# RCJS_ComMod_Helios_250821A.net
KiCad netlist of a schematic drawn in EasyEDA Pro
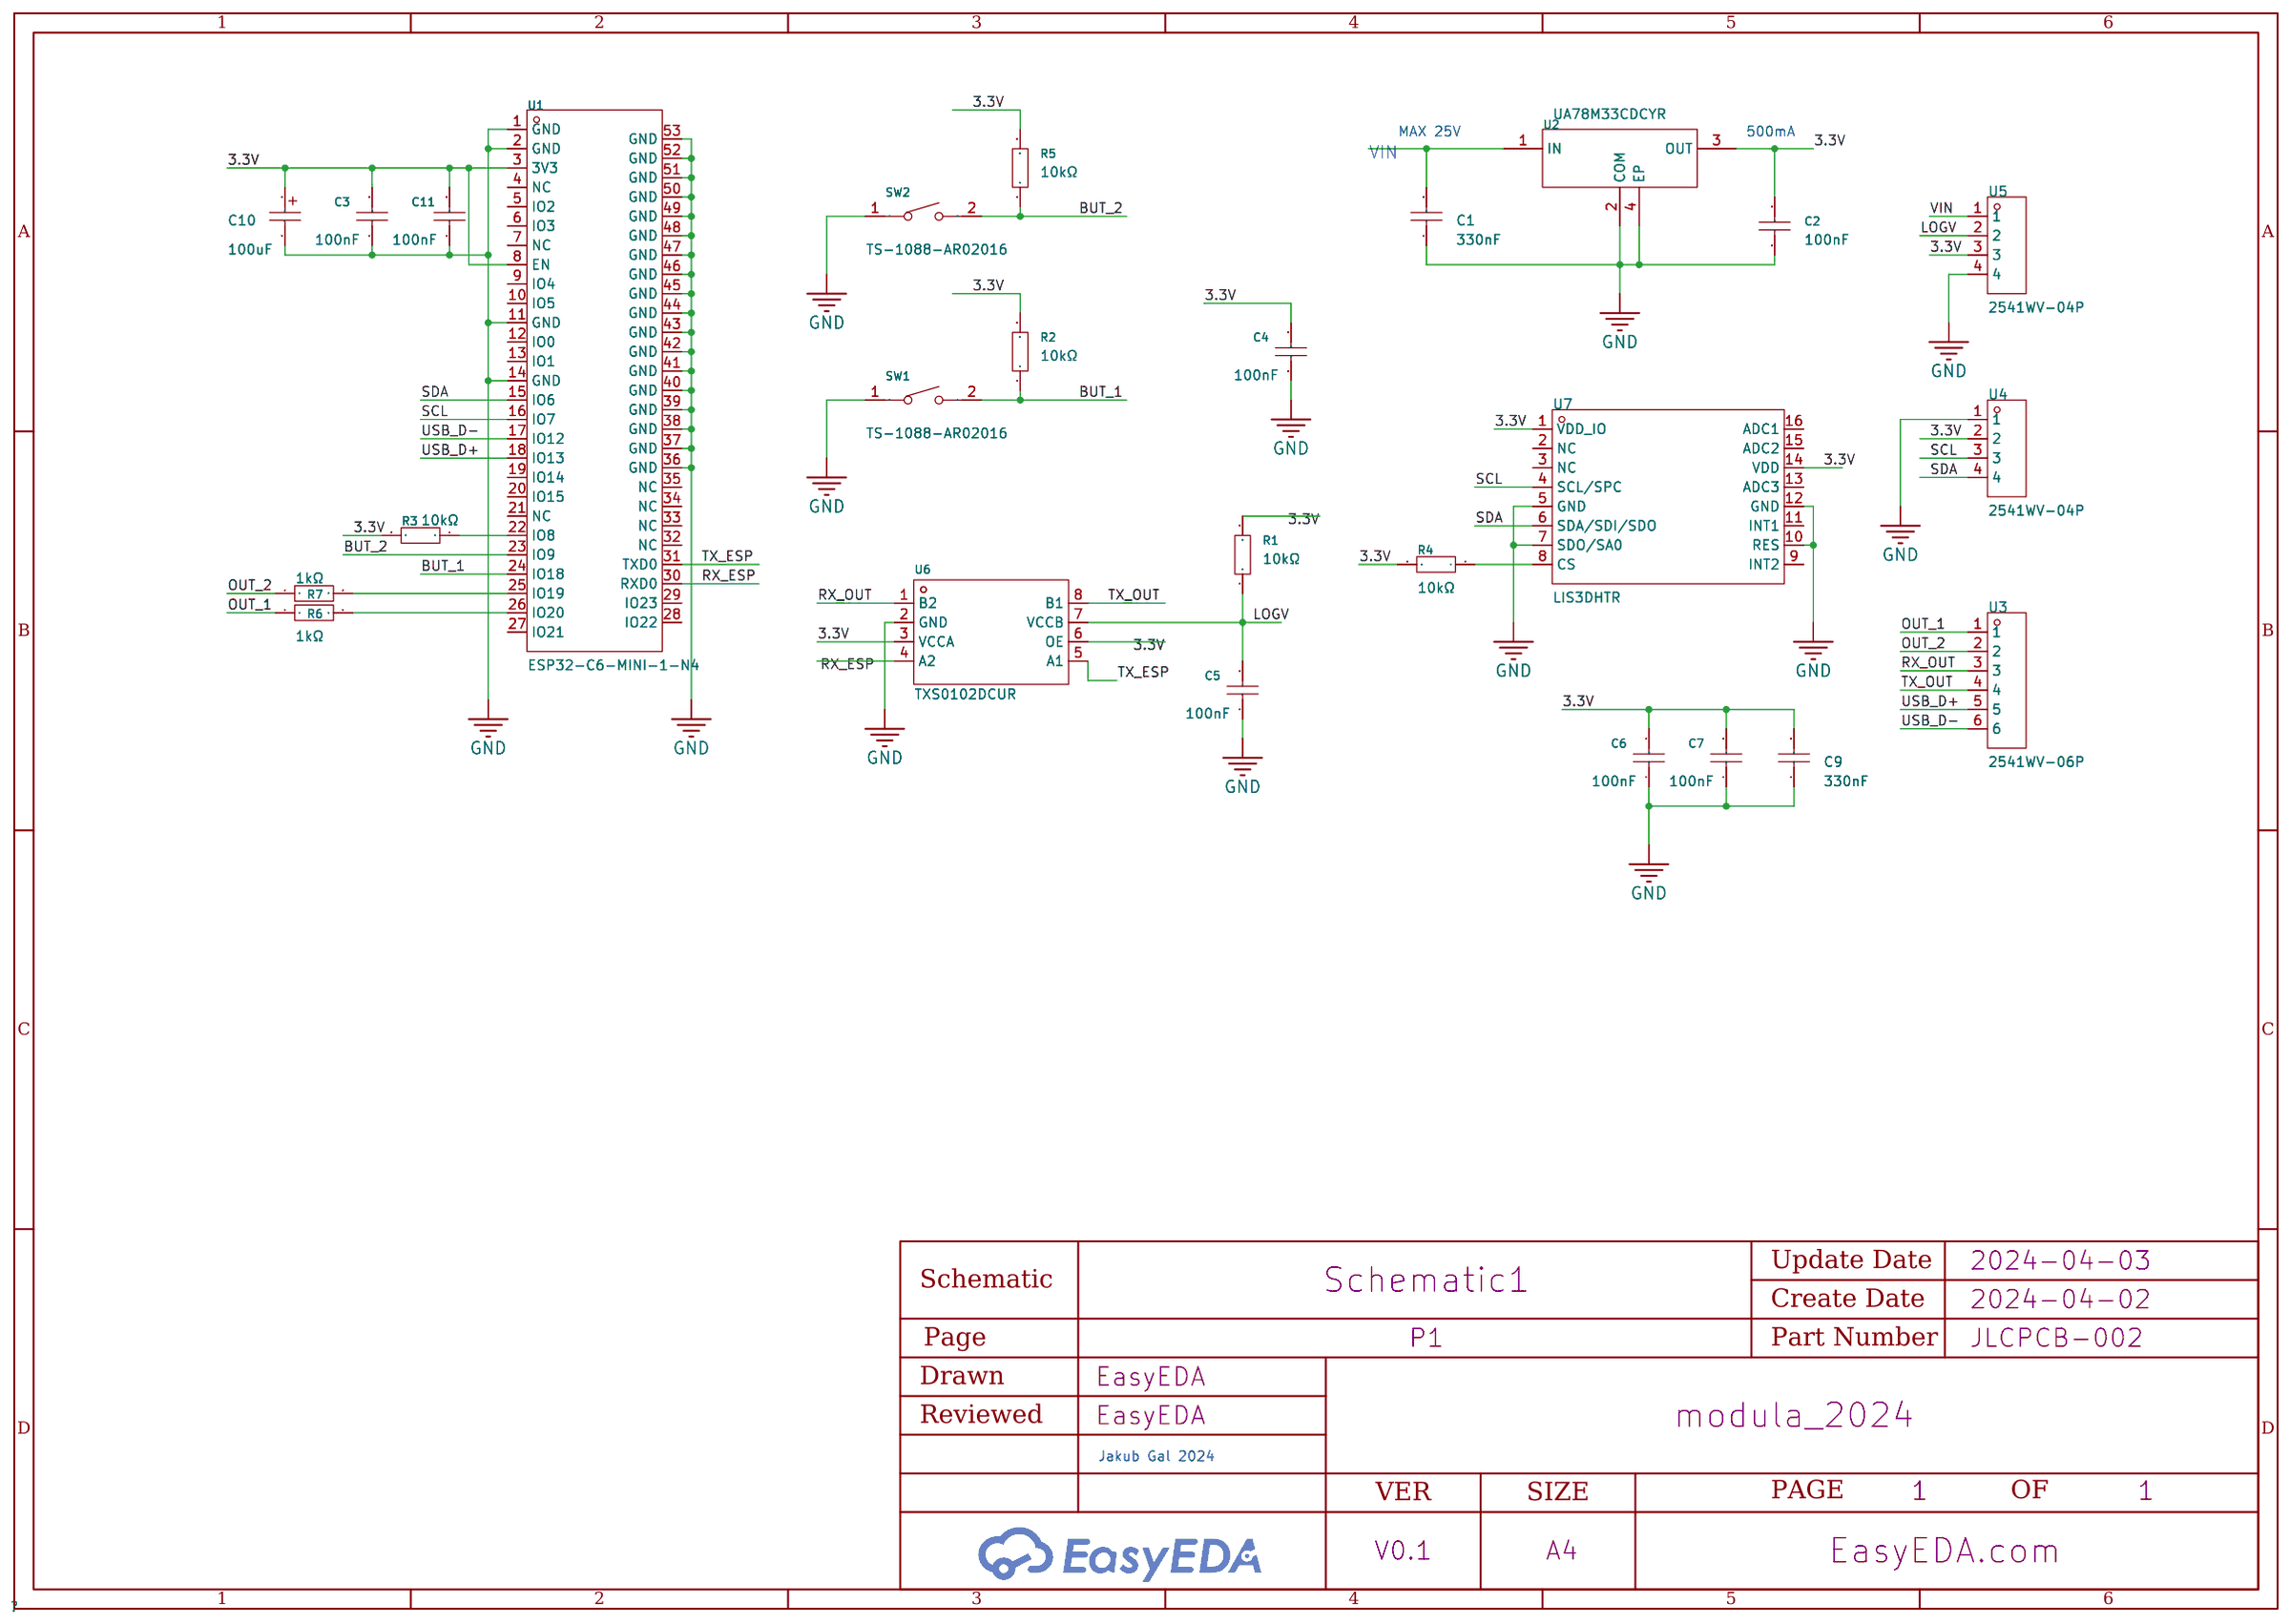
[diagram p0: schematic sheet]

(export (version "E")
  (design (tool "Eeschema 10.0.6"))
  (components
    (comp (ref "C1")
      (value "330nF")
      (footprint "easyedapro:C0805")
      (fields (field (name "Manufacturer Part") "0805B334K500NT") (field (name "Manufacturer") "FH(风华)"))
      (libsource (lib "easyedapro") (part "0805B334K500NT"))
    )
    (comp (ref "C2")
      (value "100nF")
      (footprint "easyedapro:C0603")
      (fields (field (name "Manufacturer Part") "0603B104K500NT") (field (name "Manufacturer") "FH(风华)"))
      (libsource (lib "easyedapro") (part "0603B104K500NT"))
    )
    (comp (ref "C3")
      (value "100nF")
      (footprint "easyedapro:C0603")
      (fields (field (name "Manufacturer Part") "0603B104K500NT") (field (name "Manufacturer") "FH(风华)"))
      (libsource (lib "easyedapro") (part "0603B104K500NT"))
    )
    (comp (ref "C4")
      (value "100nF")
      (footprint "easyedapro:C0603")
      (fields (field (name "Manufacturer Part") "0603B104K500NT") (field (name "Manufacturer") "FH(风华)"))
      (libsource (lib "easyedapro") (part "0603B104K500NT"))
    )
    (comp (ref "C5")
      (value "100nF")
      (footprint "easyedapro:C0603")
      (fields (field (name "Manufacturer Part") "0603B104K500NT") (field (name "Manufacturer") "FH(风华)"))
      (libsource (lib "easyedapro") (part "0603B104K500NT"))
    )
    (comp (ref "C6")
      (value "100nF")
      (footprint "easyedapro:C0603")
      (fields (field (name "Manufacturer Part") "0603B104K500NT") (field (name "Manufacturer") "FH(风华)"))
      (libsource (lib "easyedapro") (part "0603B104K500NT"))
    )
    (comp (ref "C7")
      (value "100nF")
      (footprint "easyedapro:C0603")
      (fields (field (name "Manufacturer Part") "0603B104K500NT") (field (name "Manufacturer") "FH(风华)"))
      (libsource (lib "easyedapro") (part "0603B104K500NT"))
    )
    (comp (ref "C9")
      (value "330nF")
      (footprint "easyedapro:C0805")
      (fields (field (name "Manufacturer Part") "0805B334K500NT") (field (name "Manufacturer") "FH(风华)"))
      (libsource (lib "easyedapro") (part "0805B334K500NT"))
    )
    (comp (ref "C10")
      (value "100uF")
      (footprint "easyedapro:CAP-SMD_L3.5-W2.8-R-RD")
      (fields
        (field (name "Manufacturer Part") "CA45-B-6.3V-100uF-K")
        (field (name "Manufacturer") "CEC(振华新云)")
      )
      (libsource (lib "easyedapro") (part "CA45-B-6.3V-100UF-K"))
    )
    (comp (ref "C11")
      (value "100nF")
      (footprint "easyedapro:C0603")
      (fields (field (name "Manufacturer Part") "0603B104K500NT") (field (name "Manufacturer") "FH(风华)"))
      (libsource (lib "easyedapro") (part "0603B104K500NT"))
    )
    (comp (ref "R1")
      (value "10kΩ")
      (footprint "easyedapro:R0603")
      (fields
        (field (name "Manufacturer Part") "0603WAF1002T5E")
        (field (name "Manufacturer") "UNI-ROYAL(厚声)")
      )
      (libsource (lib "easyedapro") (part "0603WAF1002T5E"))
    )
    (comp (ref "R2")
      (value "10kΩ")
      (footprint "easyedapro:R0603")
      (fields
        (field (name "Manufacturer Part") "0603WAF1002T5E")
        (field (name "Manufacturer") "UNI-ROYAL(厚声)")
      )
      (libsource (lib "easyedapro") (part "0603WAF1002T5E"))
    )
    (comp (ref "R3")
      (value "10kΩ")
      (footprint "easyedapro:R0603")
      (fields
        (field (name "Manufacturer Part") "0603WAF1002T5E")
        (field (name "Manufacturer") "UNI-ROYAL(厚声)")
      )
      (libsource (lib "easyedapro") (part "0603WAF1002T5E"))
    )
    (comp (ref "R4")
      (value "10kΩ")
      (footprint "easyedapro:R0603")
      (fields
        (field (name "Manufacturer Part") "0603WAF1002T5E")
        (field (name "Manufacturer") "UNI-ROYAL(厚声)")
      )
      (libsource (lib "easyedapro") (part "0603WAF1002T5E"))
    )
    (comp (ref "R5")
      (value "10kΩ")
      (footprint "easyedapro:R0603")
      (fields
        (field (name "Manufacturer Part") "0603WAF1002T5E")
        (field (name "Manufacturer") "UNI-ROYAL(厚声)")
      )
      (libsource (lib "easyedapro") (part "0603WAF1002T5E"))
    )
    (comp (ref "R6")
      (value "1kΩ")
      (footprint "easyedapro:R0603")
      (fields
        (field (name "Manufacturer Part") "0603WAJ0102T5E")
        (field (name "Manufacturer") "UNI-ROYAL(厚声)")
      )
      (libsource (lib "easyedapro") (part "0603WAJ0102T5E"))
    )
    (comp (ref "R7")
      (value "1kΩ")
      (footprint "easyedapro:R0603")
      (fields
        (field (name "Manufacturer Part") "0603WAJ0102T5E")
        (field (name "Manufacturer") "UNI-ROYAL(厚声)")
      )
      (libsource (lib "easyedapro") (part "0603WAJ0102T5E"))
    )
    (comp (ref "SW1")
      (value "TS-1088-AR02016")
      (footprint "easyedapro:SW-SMD_L3.9-W3.0-P4.45")
      (fields (field (name "Manufacturer") "XUNPU(讯普)"))
      (libsource (lib "easyedapro") (part "TS-1088-AR02016"))
    )
    (comp (ref "SW2")
      (value "TS-1088-AR02016")
      (footprint "easyedapro:SW-SMD_L3.9-W3.0-P4.45")
      (fields (field (name "Manufacturer") "XUNPU(讯普)"))
      (libsource (lib "easyedapro") (part "TS-1088-AR02016"))
    )
    (comp (ref "U1")
      (value "ESP32-C6-MINI-1-N4")
      (footprint "easyedapro:WIFIM-SMD_61P-L16.6-W13.2-P0.80-ESP32-C6-MINI-1-N4")
      (fields (field (name "Manufacturer") "ESPRESSIF(乐鑫)"))
      (libsource (lib "easyedapro") (part "ESP32-C6-MINI-1-N4"))
    )
    (comp (ref "U2")
      (value "UA78M33CDCYR")
      (footprint "easyedapro:SOT-223_L6.5-W3.5-P2.30-LS7.0-BR")
      (fields (field (name "Manufacturer") "TI(德州仪器)"))
      (libsource (lib "easyedapro") (part "UA78M33CDCYR"))
    )
    (comp (ref "U3")
      (value "2541WV-06P")
      (footprint "easyedapro:HDR-TH_6P-P2.54-V-M")
      (fields (field (name "Manufacturer") "HanElectricity(瀚源)"))
      (libsource (lib "easyedapro") (part "2541WV-06P"))
    )
    (comp (ref "U4")
      (value "2541WV-04P")
      (footprint "easyedapro:HDR-TH_4P-P2.54-V-M-1")
      (fields (field (name "Manufacturer") "HanElectricity(瀚源)"))
      (libsource (lib "easyedapro") (part "2541WV-04P"))
    )
    (comp (ref "U5")
      (value "2541WV-04P")
      (footprint "easyedapro:HDR-TH_4P-P2.54-V-M-1")
      (fields (field (name "Manufacturer") "HanElectricity(瀚源)"))
      (libsource (lib "easyedapro") (part "2541WV-04P"))
    )
    (comp (ref "U6")
      (value "TXS0102DCUR")
      (footprint "easyedapro:VSON8_L2.0-W2.3-P0.50-LS3.1-BL")
      (fields (field (name "Manufacturer") "TI(德州仪器)"))
      (libsource (lib "easyedapro") (part "TXS0102DCUR"))
    )
    (comp (ref "U7")
      (value "LIS3DHTR")
      (footprint "easyedapro:LGA-16_L3.0-W3.0-P0.50-TL")
      (fields (field (name "Manufacturer") "ST(意法半导体)"))
      (libsource (lib "easyedapro") (part "LIS3DHTR_C15134"))
    )
  )
  (nets
    (net (code "1") (name "/3.3V") (class "Default")
      (node (ref "C10") (pin "1") (pinfunction "1_1") (pintype "input"))
      (node (ref "C11") (pin "2") (pinfunction "2_2") (pintype "input"))
      (node (ref "C2") (pin "2") (pinfunction "2_2") (pintype "input"))
      (node (ref "C3") (pin "2") (pinfunction "2_2") (pintype "input"))
      (node (ref "C4") (pin "2") (pinfunction "2_2") (pintype "input"))
      (node (ref "C6") (pin "2") (pinfunction "2_2") (pintype "input"))
      (node (ref "C7") (pin "2") (pinfunction "2_2") (pintype "input"))
      (node (ref "C9") (pin "2") (pinfunction "2_2") (pintype "input"))
      (node (ref "R1") (pin "2") (pinfunction "2_2") (pintype "input"))
      (node (ref "R2") (pin "2") (pinfunction "2_2") (pintype "input"))
      (node (ref "R3") (pin "2") (pinfunction "2_2") (pintype "input"))
      (node (ref "R4") (pin "2") (pinfunction "2_2") (pintype "input"))
      (node (ref "R5") (pin "2") (pinfunction "2_2") (pintype "input"))
      (node (ref "U1") (pin "3") (pinfunction "3V3_3") (pintype "input"))
      (node (ref "U1") (pin "8") (pinfunction "EN_8") (pintype "input"))
      (node (ref "U2") (pin "3") (pinfunction "OUT_3") (pintype "input"))
      (node (ref "U4") (pin "2") (pinfunction "2_2") (pintype "input"))
      (node (ref "U5") (pin "3") (pinfunction "3_3") (pintype "input"))
      (node (ref "U6") (pin "3") (pinfunction "VCCA_3") (pintype "input"))
      (node (ref "U6") (pin "6") (pinfunction "OE_6") (pintype "input"))
      (node (ref "U7") (pin "1") (pinfunction "VDD_IO_1") (pintype "unspecified"))
      (node (ref "U7") (pin "14") (pinfunction "VDD_14") (pintype "unspecified"))
    )
    (net (code "2") (name "/BUT_1") (class "Default")
      (node (ref "R2") (pin "1") (pinfunction "1_1") (pintype "input"))
      (node (ref "SW1") (pin "2") (pinfunction "2_2") (pintype "input"))
      (node (ref "U1") (pin "24") (pinfunction "IO18_24") (pintype "input"))
    )
    (net (code "3") (name "/BUT_2") (class "Default")
      (node (ref "R5") (pin "1") (pinfunction "1_1") (pintype "input"))
      (node (ref "SW2") (pin "2") (pinfunction "2_2") (pintype "input"))
      (node (ref "U1") (pin "23") (pinfunction "IO9_23") (pintype "input"))
    )
    (net (code "4") (name "/LOGV") (class "Default")
      (node (ref "C5") (pin "2") (pinfunction "2_2") (pintype "input"))
      (node (ref "R1") (pin "1") (pinfunction "1_1") (pintype "input"))
      (node (ref "U5") (pin "2") (pinfunction "2_2") (pintype "input"))
      (node (ref "U6") (pin "7") (pinfunction "VCCB_7") (pintype "input"))
    )
    (net (code "5") (name "/OUT_1") (class "Default")
      (node (ref "R6") (pin "1") (pinfunction "1_1") (pintype "input"))
      (node (ref "U3") (pin "1") (pinfunction "1_1") (pintype "unspecified"))
    )
    (net (code "6") (name "/OUT_2") (class "Default")
      (node (ref "R7") (pin "1") (pinfunction "1_1") (pintype "input"))
      (node (ref "U3") (pin "2") (pinfunction "2_2") (pintype "unspecified"))
    )
    (net (code "7") (name "/RX_ESP") (class "Default")
      (node (ref "U1") (pin "30") (pinfunction "RXD0_30") (pintype "input"))
      (node (ref "U6") (pin "4") (pinfunction "A2_4") (pintype "input"))
    )
    (net (code "8") (name "/RX_OUT") (class "Default")
      (node (ref "U3") (pin "3") (pinfunction "3_3") (pintype "unspecified"))
      (node (ref "U6") (pin "1") (pinfunction "B2_1") (pintype "input"))
    )
    (net (code "9") (name "/SCL") (class "Default")
      (node (ref "U1") (pin "16") (pinfunction "IO7_16") (pintype "input"))
      (node (ref "U4") (pin "3") (pinfunction "3_3") (pintype "input"))
      (node (ref "U7") (pin "4") (pinfunction "SCL/SPC_4") (pintype "unspecified"))
    )
    (net (code "10") (name "/SDA") (class "Default")
      (node (ref "U1") (pin "15") (pinfunction "IO6_15") (pintype "input"))
      (node (ref "U4") (pin "4") (pinfunction "4_4") (pintype "input"))
      (node (ref "U7") (pin "6") (pinfunction "SDA/SDI/SDO_6") (pintype "unspecified"))
    )
    (net (code "11") (name "/TX_ESP") (class "Default")
      (node (ref "U1") (pin "31") (pinfunction "TXD0_31") (pintype "input"))
      (node (ref "U6") (pin "5") (pinfunction "A1_5") (pintype "input"))
    )
    (net (code "12") (name "/TX_OUT") (class "Default")
      (node (ref "U3") (pin "4") (pinfunction "4_4") (pintype "unspecified"))
      (node (ref "U6") (pin "8") (pinfunction "B1_8") (pintype "input"))
    )
    (net (code "13") (name "/USB_D+") (class "Default")
      (node (ref "U1") (pin "18") (pinfunction "IO13_18") (pintype "input"))
      (node (ref "U3") (pin "5") (pinfunction "5_5") (pintype "unspecified"))
    )
    (net (code "14") (name "/USB_D-") (class "Default")
      (node (ref "U1") (pin "17") (pinfunction "IO12_17") (pintype "input"))
      (node (ref "U3") (pin "6") (pinfunction "6_6") (pintype "unspecified"))
    )
    (net (code "15") (name "/VIN") (class "Default")
      (node (ref "C1") (pin "2") (pinfunction "2_2") (pintype "input"))
      (node (ref "U2") (pin "1") (pinfunction "IN_1") (pintype "input"))
      (node (ref "U5") (pin "1") (pinfunction "1_1") (pintype "input"))
    )
    (net (code "16") (name "GND") (class "Default")
      (node (ref "C1") (pin "1") (pinfunction "1_1") (pintype "input"))
      (node (ref "C10") (pin "2") (pinfunction "2_2") (pintype "input"))
      (node (ref "C11") (pin "1") (pinfunction "1_1") (pintype "input"))
      (node (ref "C2") (pin "1") (pinfunction "1_1") (pintype "input"))
      (node (ref "C3") (pin "1") (pinfunction "1_1") (pintype "input"))
      (node (ref "C4") (pin "1") (pinfunction "1_1") (pintype "input"))
      (node (ref "C5") (pin "1") (pinfunction "1_1") (pintype "input"))
      (node (ref "C6") (pin "1") (pinfunction "1_1") (pintype "input"))
      (node (ref "C7") (pin "1") (pinfunction "1_1") (pintype "input"))
      (node (ref "C9") (pin "1") (pinfunction "1_1") (pintype "input"))
      (node (ref "SW1") (pin "1") (pinfunction "1_1") (pintype "input"))
      (node (ref "SW2") (pin "1") (pinfunction "1_1") (pintype "input"))
      (node (ref "U1") (pin "1") (pinfunction "GND_1") (pintype "input"))
      (node (ref "U1") (pin "11") (pinfunction "GND_11") (pintype "input"))
      (node (ref "U1") (pin "14") (pinfunction "GND_14") (pintype "input"))
      (node (ref "U1") (pin "2") (pinfunction "GND_2") (pintype "input"))
      (node (ref "U1") (pin "36") (pinfunction "GND_36") (pintype "input"))
      (node (ref "U1") (pin "37") (pinfunction "GND_37") (pintype "input"))
      (node (ref "U1") (pin "38") (pinfunction "GND_38") (pintype "input"))
      (node (ref "U1") (pin "39") (pinfunction "GND_39") (pintype "input"))
      (node (ref "U1") (pin "40") (pinfunction "GND_40") (pintype "input"))
      (node (ref "U1") (pin "41") (pinfunction "GND_41") (pintype "input"))
      (node (ref "U1") (pin "42") (pinfunction "GND_42") (pintype "input"))
      (node (ref "U1") (pin "43") (pinfunction "GND_43") (pintype "input"))
      (node (ref "U1") (pin "44") (pinfunction "GND_44") (pintype "input"))
      (node (ref "U1") (pin "45") (pinfunction "GND_45") (pintype "input"))
      (node (ref "U1") (pin "46") (pinfunction "GND_46") (pintype "input"))
      (node (ref "U1") (pin "47") (pinfunction "GND_47") (pintype "input"))
      (node (ref "U1") (pin "48") (pinfunction "GND_48") (pintype "input"))
      (node (ref "U1") (pin "49") (pinfunction "GND_49") (pintype "input"))
      (node (ref "U1") (pin "50") (pinfunction "GND_50") (pintype "input"))
      (node (ref "U1") (pin "51") (pinfunction "GND_51") (pintype "input"))
      (node (ref "U1") (pin "52") (pinfunction "GND_52") (pintype "input"))
      (node (ref "U1") (pin "53") (pinfunction "GND_53") (pintype "input"))
      (node (ref "U2") (pin "2") (pinfunction "COM_2") (pintype "input"))
      (node (ref "U2") (pin "4") (pinfunction "EP_4") (pintype "input"))
      (node (ref "U4") (pin "1") (pinfunction "1_1") (pintype "input"))
      (node (ref "U5") (pin "4") (pinfunction "4_4") (pintype "input"))
      (node (ref "U6") (pin "2") (pinfunction "GND_2") (pintype "input"))
      (node (ref "U7") (pin "10") (pinfunction "RES_10") (pintype "unspecified"))
      (node (ref "U7") (pin "12") (pinfunction "GND_12") (pintype "unspecified"))
      (node (ref "U7") (pin "5") (pinfunction "GND_5") (pintype "unspecified"))
      (node (ref "U7") (pin "7") (pinfunction "SDO/SA0_7") (pintype "unspecified"))
    )
    (net (code "17") (name "Net-(U1-IO8)") (class "Default")
      (node (ref "R3") (pin "1") (pinfunction "1_1") (pintype "input"))
      (node (ref "U1") (pin "22") (pinfunction "IO8_22") (pintype "input"))
    )
    (net (code "18") (name "Net-(U1-IO19)") (class "Default")
      (node (ref "R7") (pin "2") (pinfunction "2_2") (pintype "input"))
      (node (ref "U1") (pin "25") (pinfunction "IO19_25") (pintype "input"))
    )
    (net (code "19") (name "Net-(U1-IO20)") (class "Default")
      (node (ref "R6") (pin "2") (pinfunction "2_2") (pintype "input"))
      (node (ref "U1") (pin "26") (pinfunction "IO20_26") (pintype "input"))
    )
    (net (code "20") (name "Net-(U7-CS)") (class "Default")
      (node (ref "R4") (pin "1") (pinfunction "1_1") (pintype "input"))
      (node (ref "U7") (pin "8") (pinfunction "CS_8") (pintype "unspecified"))
    )
    (net (code "21") (name "unconnected-(U1-IO0-Pad12)") (class "Default")
      (node (ref "U1") (pin "12") (pinfunction "IO0_12") (pintype "input"))
    )
    (net (code "22") (name "unconnected-(U1-IO1-Pad13)") (class "Default")
      (node (ref "U1") (pin "13") (pinfunction "IO1_13") (pintype "input"))
    )
    (net (code "23") (name "unconnected-(U1-IO2-Pad5)") (class "Default")
      (node (ref "U1") (pin "5") (pinfunction "IO2_5") (pintype "input"))
    )
    (net (code "24") (name "unconnected-(U1-IO3-Pad6)") (class "Default")
      (node (ref "U1") (pin "6") (pinfunction "IO3_6") (pintype "input"))
    )
    (net (code "25") (name "unconnected-(U1-IO4-Pad9)") (class "Default")
      (node (ref "U1") (pin "9") (pinfunction "IO4_9") (pintype "input"))
    )
    (net (code "26") (name "unconnected-(U1-IO5-Pad10)") (class "Default")
      (node (ref "U1") (pin "10") (pinfunction "IO5_10") (pintype "input"))
    )
    (net (code "27") (name "unconnected-(U1-IO14-Pad19)") (class "Default")
      (node (ref "U1") (pin "19") (pinfunction "IO14_19") (pintype "input"))
    )
    (net (code "28") (name "unconnected-(U1-IO15-Pad20)") (class "Default")
      (node (ref "U1") (pin "20") (pinfunction "IO15_20") (pintype "input"))
    )
    (net (code "29") (name "unconnected-(U1-IO21-Pad27)") (class "Default")
      (node (ref "U1") (pin "27") (pinfunction "IO21_27") (pintype "input"))
    )
    (net (code "30") (name "unconnected-(U1-IO22-Pad28)") (class "Default")
      (node (ref "U1") (pin "28") (pinfunction "IO22_28") (pintype "input"))
    )
    (net (code "31") (name "unconnected-(U1-IO23-Pad29)") (class "Default")
      (node (ref "U1") (pin "29") (pinfunction "IO23_29") (pintype "input"))
    )
    (net (code "32") (name "unconnected-(U1-NC-Pad4)") (class "Default")
      (node (ref "U1") (pin "4") (pinfunction "NC_4") (pintype "input"))
    )
    (net (code "33") (name "unconnected-(U1-NC-Pad7)") (class "Default")
      (node (ref "U1") (pin "7") (pinfunction "NC_7") (pintype "input"))
    )
    (net (code "34") (name "unconnected-(U1-NC-Pad21)") (class "Default")
      (node (ref "U1") (pin "21") (pinfunction "NC_21") (pintype "input"))
    )
    (net (code "35") (name "unconnected-(U1-NC-Pad32)") (class "Default")
      (node (ref "U1") (pin "32") (pinfunction "NC_32") (pintype "input"))
    )
    (net (code "36") (name "unconnected-(U1-NC-Pad33)") (class "Default")
      (node (ref "U1") (pin "33") (pinfunction "NC_33") (pintype "input"))
    )
    (net (code "37") (name "unconnected-(U1-NC-Pad34)") (class "Default")
      (node (ref "U1") (pin "34") (pinfunction "NC_34") (pintype "input"))
    )
    (net (code "38") (name "unconnected-(U1-NC-Pad35)") (class "Default")
      (node (ref "U1") (pin "35") (pinfunction "NC_35") (pintype "input"))
    )
    (net (code "39") (name "unconnected-(U7-ADC1-Pad16)") (class "Default")
      (node (ref "U7") (pin "16") (pinfunction "ADC1_16") (pintype "unspecified"))
    )
    (net (code "40") (name "unconnected-(U7-ADC2-Pad15)") (class "Default")
      (node (ref "U7") (pin "15") (pinfunction "ADC2_15") (pintype "unspecified"))
    )
    (net (code "41") (name "unconnected-(U7-ADC3-Pad13)") (class "Default")
      (node (ref "U7") (pin "13") (pinfunction "ADC3_13") (pintype "unspecified"))
    )
    (net (code "42") (name "unconnected-(U7-INT1-Pad11)") (class "Default")
      (node (ref "U7") (pin "11") (pinfunction "INT1_11") (pintype "unspecified"))
    )
    (net (code "43") (name "unconnected-(U7-INT2-Pad9)") (class "Default")
      (node (ref "U7") (pin "9") (pinfunction "INT2_9") (pintype "unspecified"))
    )
    (net (code "44") (name "unconnected-(U7-NC-Pad2)") (class "Default")
      (node (ref "U7") (pin "2") (pinfunction "NC_2") (pintype "unspecified"))
    )
    (net (code "45") (name "unconnected-(U7-NC-Pad3)") (class "Default")
      (node (ref "U7") (pin "3") (pinfunction "NC_3") (pintype "unspecified"))
    )
  )
)
